# E4m.net
KiCad netlist of a schematic drawn in EAGLE
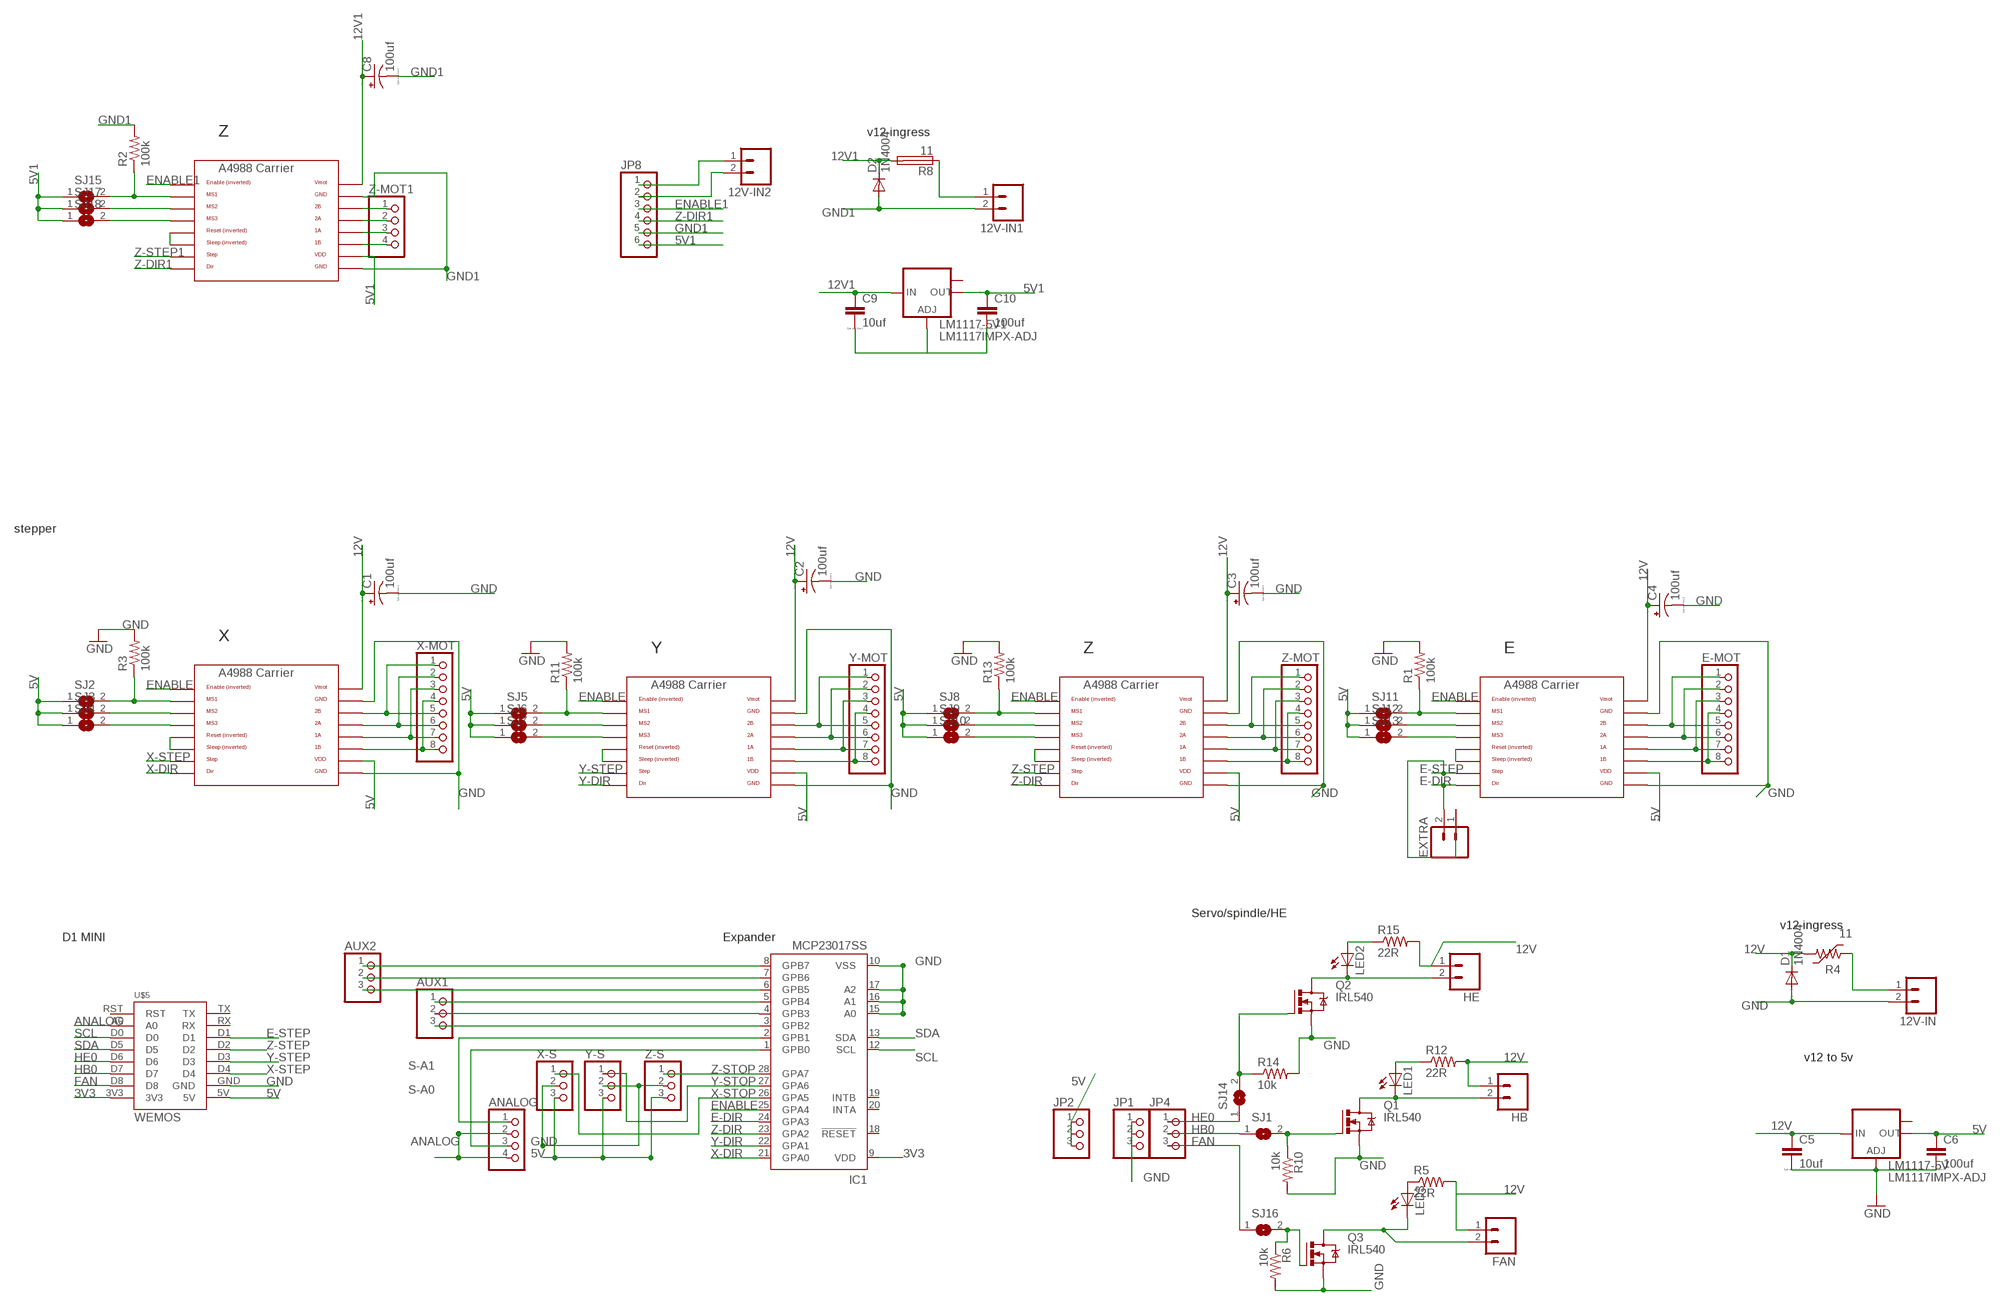
[diagram p0: schematic, sheet 1]

(export (version "E")
  (design (tool "Eeschema 10.0.6"))
  (components
    (comp (ref "12V-IN")
      (value "M02PTH")
      (footprint "eagle-import:1X02")
      (libsource (lib "eagle-import") (part "M02PTH"))
    )
    (comp (ref "12V-IN1")
      (value "M02PTH")
      (footprint "eagle-import:1X02")
      (libsource (lib "eagle-import") (part "M02PTH"))
    )
    (comp (ref "12V-IN2")
      (value "M02PTH")
      (footprint "eagle-import:1X02")
      (libsource (lib "eagle-import") (part "M02PTH"))
    )
    (comp (ref "ANALOG")
      (value "PINHD-1X4")
      (footprint "eagle-import:1X04")
      (libsource (lib "eagle-import") (part "PINHD-1X4"))
    )
    (comp (ref "AUX1")
      (value "PINHD-1X3CB")
      (footprint "eagle-import:1X03-CLEANBIG")
      (libsource (lib "eagle-import") (part "PINHD-1X3CB"))
    )
    (comp (ref "AUX2")
      (value "PINHD-1X3CB")
      (footprint "eagle-import:1X03-CLEANBIG")
      (libsource (lib "eagle-import") (part "PINHD-1X3CB"))
    )
    (comp (ref "C1")
      (value "100uf")
      (footprint "eagle-import:153CLV-0605")
      (libsource (lib "eagle-import") (part "CPOL-US153CLV-0605"))
    )
    (comp (ref "C2")
      (value "100uf")
      (footprint "eagle-import:153CLV-0605")
      (libsource (lib "eagle-import") (part "CPOL-US153CLV-0605"))
    )
    (comp (ref "C3")
      (value "100uf")
      (footprint "eagle-import:153CLV-0605")
      (libsource (lib "eagle-import") (part "CPOL-US153CLV-0605"))
    )
    (comp (ref "C4")
      (value "100uf")
      (footprint "eagle-import:153CLV-0605")
      (libsource (lib "eagle-import") (part "CPOL-US153CLV-0605"))
    )
    (comp (ref "C5")
      (value "10uf")
      (footprint "eagle-import:C0805")
      (libsource (lib "eagle-import") (part "C"))
    )
    (comp (ref "C6")
      (value "100uf")
      (footprint "eagle-import:C0805")
      (libsource (lib "eagle-import") (part "C"))
    )
    (comp (ref "C8")
      (value "100uf")
      (footprint "eagle-import:153CLV-0605")
      (libsource (lib "eagle-import") (part "CPOL-US153CLV-0605"))
    )
    (comp (ref "C9")
      (value "10uf")
      (footprint "eagle-import:C0603")
      (libsource (lib "eagle-import") (part "CC0603"))
    )
    (comp (ref "C10")
      (value "100uf")
      (footprint "eagle-import:C0603")
      (libsource (lib "eagle-import") (part "CC0603"))
    )
    (comp (ref "D1")
      (value "1N4004")
      (footprint "eagle-import:DO41-10")
      (libsource (lib "eagle-import") (part "1N4004"))
    )
    (comp (ref "D2")
      (value "1N4004")
      (footprint "eagle-import:DO41-10")
      (libsource (lib "eagle-import") (part "1N4004"))
    )
    (comp (ref "E-MOT")
      (value "PINHD-1X8CLEANBIG")
      (footprint "eagle-import:1X08-CLEANBIG")
      (libsource (lib "eagle-import") (part "PINHD-1X8CLEANBIG"))
    )
    (comp (ref "EXTRA")
      (value "M02PTH")
      (footprint "eagle-import:1X02")
      (libsource (lib "eagle-import") (part "M02PTH"))
    )
    (comp (ref "FAN")
      (value "M02PTH")
      (footprint "eagle-import:1X02")
      (libsource (lib "eagle-import") (part "M02PTH"))
    )
    (comp (ref "HB")
      (value "M02PTH")
      (footprint "eagle-import:1X02")
      (libsource (lib "eagle-import") (part "M02PTH"))
    )
    (comp (ref "HE")
      (value "M02PTH")
      (footprint "eagle-import:1X02")
      (libsource (lib "eagle-import") (part "M02PTH"))
    )
    (comp (ref "IC1")
      (value "MCP23017SS")
      (footprint "eagle-import:SSOP28")
      (libsource (lib "eagle-import") (part "MCP23017SS"))
    )
    (comp (ref "JP1")
      (value "PINHD-1X3CB")
      (footprint "eagle-import:1X03-CLEANBIG")
      (libsource (lib "eagle-import") (part "PINHD-1X3CB"))
    )
    (comp (ref "JP2")
      (value "PINHD-1X3CB")
      (footprint "eagle-import:1X03-CLEANBIG")
      (libsource (lib "eagle-import") (part "PINHD-1X3CB"))
    )
    (comp (ref "JP4")
      (value "PINHD-1X3CB")
      (footprint "eagle-import:1X03-CLEANBIG")
      (libsource (lib "eagle-import") (part "PINHD-1X3CB"))
    )
    (comp (ref "JP8")
      (value "PINHD-1X6")
      (footprint "eagle-import:1X06")
      (libsource (lib "eagle-import") (part "PINHD-1X6"))
    )
    (comp (ref "LED1")
      (value "LEDCHIP-LED0805")
      (footprint "eagle-import:CHIP-LED0805")
      (libsource (lib "eagle-import") (part "LEDCHIP-LED0805"))
    )
    (comp (ref "LED2")
      (value "LEDCHIP-LED0805")
      (footprint "eagle-import:CHIP-LED0805")
      (libsource (lib "eagle-import") (part "LEDCHIP-LED0805"))
    )
    (comp (ref "LED3")
      (value "LEDCHIP-LED0805")
      (footprint "eagle-import:CHIP-LED0805")
      (libsource (lib "eagle-import") (part "LEDCHIP-LED0805"))
    )
    (comp (ref "LM1117-5V")
      (value "LM1117IMPX-ADJ")
      (footprint "eagle-import:SOT223")
      (libsource (lib "eagle-import") (part "LM1117IMPX-ADJ"))
    )
    (comp (ref "LM1117-5V1")
      (value "LM1117IMPX-ADJ")
      (footprint "eagle-import:SOT223")
      (libsource (lib "eagle-import") (part "LM1117IMPX-ADJ"))
    )
    (comp (ref "Q1")
      (value "IRL540")
      (footprint "eagle-import:TO220BV")
      (libsource (lib "eagle-import") (part "IRF540"))
    )
    (comp (ref "Q2")
      (value "IRL540")
      (footprint "eagle-import:TO220BV")
      (libsource (lib "eagle-import") (part "IRF540"))
    )
    (comp (ref "Q3")
      (value "IRL540")
      (footprint "eagle-import:TO220BV")
      (libsource (lib "eagle-import") (part "IRF540"))
    )
    (comp (ref "R1")
      (value "100k")
      (footprint "eagle-import:R0805")
      (libsource (lib "eagle-import") (part "R-US_R0805"))
    )
    (comp (ref "R2")
      (value "100k")
      (footprint "eagle-import:R0805")
      (libsource (lib "eagle-import") (part "R-US_R0805"))
    )
    (comp (ref "R3")
      (value "100k")
      (footprint "eagle-import:R0805")
      (libsource (lib "eagle-import") (part "R-US_R0805"))
    )
    (comp (ref "R4")
      (value "11")
      (footprint "eagle-import:PF-8.0")
      (libsource (lib "eagle-import") (part "PTC-PF-8.0"))
    )
    (comp (ref "R5")
      (value "22R")
      (footprint "eagle-import:R0805")
      (libsource (lib "eagle-import") (part "R-US_R0805"))
    )
    (comp (ref "R6")
      (value "10k")
      (footprint "eagle-import:R0805")
      (libsource (lib "eagle-import") (part "R-US_R0805"))
    )
    (comp (ref "R8")
      (value "11")
      (footprint "eagle-import:LITTLEFUSE")
      (libsource (lib "eagle-import") (part "PTCFUSE"))
    )
    (comp (ref "R10")
      (value "10k")
      (footprint "eagle-import:R0805")
      (libsource (lib "eagle-import") (part "R-US_R0805"))
    )
    (comp (ref "R11")
      (value "100k")
      (footprint "eagle-import:R0805")
      (libsource (lib "eagle-import") (part "R-US_R0805"))
    )
    (comp (ref "R12")
      (value "22R")
      (footprint "eagle-import:R0805")
      (libsource (lib "eagle-import") (part "R-US_R0805"))
    )
    (comp (ref "R13")
      (value "100k")
      (footprint "eagle-import:R0805")
      (libsource (lib "eagle-import") (part "R-US_R0805"))
    )
    (comp (ref "R14")
      (value "10k")
      (footprint "eagle-import:R0805")
      (libsource (lib "eagle-import") (part "R-US_R0805"))
    )
    (comp (ref "R15")
      (value "22R")
      (footprint "eagle-import:R0805")
      (libsource (lib "eagle-import") (part "R-US_R0805"))
    )
    (comp (ref "SJ1") (value "SJ") (footprint "eagle-import:SJ") (libsource (lib "eagle-import") (part "SJ")))
    (comp (ref "SJ2") (value "SJ") (footprint "eagle-import:SJ") (libsource (lib "eagle-import") (part "SJ")))
    (comp (ref "SJ3") (value "SJ") (footprint "eagle-import:SJ") (libsource (lib "eagle-import") (part "SJ")))
    (comp (ref "SJ4") (value "SJ") (footprint "eagle-import:SJ") (libsource (lib "eagle-import") (part "SJ")))
    (comp (ref "SJ5") (value "SJ") (footprint "eagle-import:SJ") (libsource (lib "eagle-import") (part "SJ")))
    (comp (ref "SJ6") (value "SJ") (footprint "eagle-import:SJ") (libsource (lib "eagle-import") (part "SJ")))
    (comp (ref "SJ7") (value "SJ") (footprint "eagle-import:SJ") (libsource (lib "eagle-import") (part "SJ")))
    (comp (ref "SJ8") (value "SJ") (footprint "eagle-import:SJ") (libsource (lib "eagle-import") (part "SJ")))
    (comp (ref "SJ9") (value "SJ") (footprint "eagle-import:SJ") (libsource (lib "eagle-import") (part "SJ")))
    (comp (ref "SJ10")
      (value "SJ")
      (footprint "eagle-import:SJ")
      (libsource (lib "eagle-import") (part "SJ"))
    )
    (comp (ref "SJ11")
      (value "SJ")
      (footprint "eagle-import:SJ")
      (libsource (lib "eagle-import") (part "SJ"))
    )
    (comp (ref "SJ12")
      (value "SJ")
      (footprint "eagle-import:SJ")
      (libsource (lib "eagle-import") (part "SJ"))
    )
    (comp (ref "SJ13")
      (value "SJ")
      (footprint "eagle-import:SJ")
      (libsource (lib "eagle-import") (part "SJ"))
    )
    (comp (ref "SJ14")
      (value "SJ")
      (footprint "eagle-import:SJ")
      (libsource (lib "eagle-import") (part "SJ"))
    )
    (comp (ref "SJ15")
      (value "SJ")
      (footprint "eagle-import:SJ")
      (libsource (lib "eagle-import") (part "SJ"))
    )
    (comp (ref "SJ16")
      (value "SJ")
      (footprint "eagle-import:SJ")
      (libsource (lib "eagle-import") (part "SJ"))
    )
    (comp (ref "SJ17")
      (value "SJ")
      (footprint "eagle-import:SJ")
      (libsource (lib "eagle-import") (part "SJ"))
    )
    (comp (ref "SJ18")
      (value "SJ")
      (footprint "eagle-import:SJ")
      (libsource (lib "eagle-import") (part "SJ"))
    )
    (comp (ref "U$1")
      (value "A4988BREAKOUT")
      (footprint "eagle-import:A4988BREAKOUT")
      (libsource (lib "eagle-import") (part "A4988BREAKOUT"))
    )
    (comp (ref "U$2")
      (value "A4988BREAKOUT")
      (footprint "eagle-import:A4988BREAKOUT")
      (libsource (lib "eagle-import") (part "A4988BREAKOUT"))
    )
    (comp (ref "U$3")
      (value "A4988BREAKOUT")
      (footprint "eagle-import:A4988BREAKOUT")
      (libsource (lib "eagle-import") (part "A4988BREAKOUT"))
    )
    (comp (ref "U$5")
      (value "WEMOS")
      (footprint "eagle-import:WEMOS")
      (libsource (lib "eagle-import") (part "WEMOS"))
    )
    (comp (ref "U$6")
      (value "A4988BREAKOUT")
      (footprint "eagle-import:A4988BREAKOUT")
      (libsource (lib "eagle-import") (part "A4988BREAKOUT"))
    )
    (comp (ref "U$9")
      (value "A4988BREAKOUT")
      (footprint "eagle-import:A4988BREAKOUT")
      (libsource (lib "eagle-import") (part "A4988BREAKOUT"))
    )
    (comp (ref "X-MOT")
      (value "PINHD-1X8CLEANBIG")
      (footprint "eagle-import:1X08-CLEANBIG")
      (libsource (lib "eagle-import") (part "PINHD-1X8CLEANBIG"))
    )
    (comp (ref "X-S")
      (value "PINHD-1X3CB")
      (footprint "eagle-import:1X03-CLEANBIG")
      (libsource (lib "eagle-import") (part "PINHD-1X3CB"))
    )
    (comp (ref "Y-MOT")
      (value "PINHD-1X8CLEANBIG")
      (footprint "eagle-import:1X08-CLEANBIG")
      (libsource (lib "eagle-import") (part "PINHD-1X8CLEANBIG"))
    )
    (comp (ref "Y-S")
      (value "PINHD-1X3CB")
      (footprint "eagle-import:1X03-CLEANBIG")
      (libsource (lib "eagle-import") (part "PINHD-1X3CB"))
    )
    (comp (ref "Z-MOT")
      (value "PINHD-1X8CLEANBIG")
      (footprint "eagle-import:1X08-CLEANBIG")
      (libsource (lib "eagle-import") (part "PINHD-1X8CLEANBIG"))
    )
    (comp (ref "Z-MOT1")
      (value "PINHD-1X4")
      (footprint "eagle-import:1X04")
      (libsource (lib "eagle-import") (part "PINHD-1X4"))
    )
    (comp (ref "Z-S")
      (value "PINHD-1X3CB")
      (footprint "eagle-import:1X03-CLEANBIG")
      (libsource (lib "eagle-import") (part "PINHD-1X3CB"))
    )
  )
  (nets
    (net (code "1") (name "/3V3") (class "Default")
      (node (ref "IC1") (pin "9") (pinfunction "VDD_9") (pintype "power_in"))
      (node (ref "U$5") (pin "3V3") (pinfunction "3V3_3V3") (pintype "bidirectional"))
    )
    (net (code "2") (name "/5V") (class "Default")
      (node (ref "C6") (pin "1") (pinfunction "1_1") (pintype "passive"))
      (node (ref "JP2") (pin "1") (pinfunction "1_1") (pintype "passive"))
      (node (ref "JP2") (pin "2") (pinfunction "2_2") (pintype "passive"))
      (node (ref "JP2") (pin "3") (pinfunction "3_3") (pintype "passive"))
      (node (ref "LM1117-5V") (pin "2") (pinfunction "OUT_2") (pintype "passive"))
      (node (ref "SJ10") (pin "1") (pinfunction "1_1") (pintype "passive"))
      (node (ref "SJ11") (pin "1") (pinfunction "1_1") (pintype "passive"))
      (node (ref "SJ12") (pin "1") (pinfunction "1_1") (pintype "passive"))
      (node (ref "SJ13") (pin "1") (pinfunction "1_1") (pintype "passive"))
      (node (ref "SJ2") (pin "1") (pinfunction "1_1") (pintype "passive"))
      (node (ref "SJ3") (pin "1") (pinfunction "1_1") (pintype "passive"))
      (node (ref "SJ4") (pin "1") (pinfunction "1_1") (pintype "passive"))
      (node (ref "SJ5") (pin "1") (pinfunction "1_1") (pintype "passive"))
      (node (ref "SJ6") (pin "1") (pinfunction "1_1") (pintype "passive"))
      (node (ref "SJ7") (pin "1") (pinfunction "1_1") (pintype "passive"))
      (node (ref "SJ8") (pin "1") (pinfunction "1_1") (pintype "passive"))
      (node (ref "SJ9") (pin "1") (pinfunction "1_1") (pintype "passive"))
      (node (ref "U$1") (pin "VDD") (pinfunction "VDD_VDD") (pintype "power_in"))
      (node (ref "U$2") (pin "VDD") (pinfunction "VDD_VDD") (pintype "power_in"))
      (node (ref "U$3") (pin "VDD") (pinfunction "VDD_VDD") (pintype "power_in"))
      (node (ref "U$5") (pin "5V") (pinfunction "5V_5V") (pintype "bidirectional"))
      (node (ref "U$9") (pin "VDD") (pinfunction "VDD_VDD") (pintype "power_in"))
      (node (ref "X-S") (pin "3") (pinfunction "3_3") (pintype "passive"))
      (node (ref "Y-S") (pin "3") (pinfunction "3_3") (pintype "passive"))
      (node (ref "Z-S") (pin "3") (pinfunction "3_3") (pintype "passive"))
    )
    (net (code "3") (name "/5V1") (class "Default")
      (node (ref "C10") (pin "1") (pinfunction "1_1") (pintype "passive"))
      (node (ref "JP8") (pin "6") (pinfunction "6_6") (pintype "passive"))
      (node (ref "LM1117-5V1") (pin "2") (pinfunction "OUT_2") (pintype "passive"))
      (node (ref "SJ15") (pin "1") (pinfunction "1_1") (pintype "passive"))
      (node (ref "SJ17") (pin "1") (pinfunction "1_1") (pintype "passive"))
      (node (ref "SJ18") (pin "1") (pinfunction "1_1") (pintype "passive"))
      (node (ref "U$6") (pin "VDD") (pinfunction "VDD_VDD") (pintype "power_in"))
    )
    (net (code "4") (name "/12V") (class "Default")
      (node (ref "C1") (pin "+") (pinfunction "+_+") (pintype "passive"))
      (node (ref "C2") (pin "+") (pinfunction "+_+") (pintype "passive"))
      (node (ref "C3") (pin "+") (pinfunction "+_+") (pintype "passive"))
      (node (ref "C4") (pin "+") (pinfunction "+_+") (pintype "passive"))
      (node (ref "C5") (pin "1") (pinfunction "1_1") (pintype "passive"))
      (node (ref "D1") (pin "C") (pinfunction "C_C") (pintype "passive"))
      (node (ref "FAN") (pin "1") (pinfunction "1_1") (pintype "passive"))
      (node (ref "HB") (pin "1") (pinfunction "1_1") (pintype "passive"))
      (node (ref "HE") (pin "1") (pinfunction "1_1") (pintype "passive"))
      (node (ref "LM1117-5V") (pin "3") (pinfunction "IN_3") (pintype "input"))
      (node (ref "R12") (pin "2") (pinfunction "2_2") (pintype "passive"))
      (node (ref "R15") (pin "2") (pinfunction "2_2") (pintype "passive"))
      (node (ref "R4") (pin "2") (pinfunction "2_2") (pintype "passive"))
      (node (ref "R5") (pin "2") (pinfunction "2_2") (pintype "passive"))
      (node (ref "U$1") (pin "VMOT") (pinfunction "VMOT_VMOT") (pintype "power_in"))
      (node (ref "U$2") (pin "VMOT") (pinfunction "VMOT_VMOT") (pintype "power_in"))
      (node (ref "U$3") (pin "VMOT") (pinfunction "VMOT_VMOT") (pintype "power_in"))
      (node (ref "U$9") (pin "VMOT") (pinfunction "VMOT_VMOT") (pintype "power_in"))
    )
    (net (code "5") (name "/12V1") (class "Default")
      (node (ref "C8") (pin "+") (pinfunction "+_+") (pintype "passive"))
      (node (ref "C9") (pin "1") (pinfunction "1_1") (pintype "passive"))
      (node (ref "D2") (pin "C") (pinfunction "C_C") (pintype "passive"))
      (node (ref "LM1117-5V1") (pin "3") (pinfunction "IN_3") (pintype "input"))
      (node (ref "R8") (pin "2") (pinfunction "2_2") (pintype "passive"))
      (node (ref "U$6") (pin "VMOT") (pinfunction "VMOT_VMOT") (pintype "power_in"))
    )
    (net (code "6") (name "/ANALOG") (class "Default")
      (node (ref "ANALOG") (pin "2") (pinfunction "2_2") (pintype "passive"))
      (node (ref "ANALOG") (pin "4") (pinfunction "4_4") (pintype "passive"))
      (node (ref "U$5") (pin "A0") (pinfunction "A0_A0") (pintype "bidirectional"))
    )
    (net (code "7") (name "/E-DIR") (class "Default")
      (node (ref "EXTRA") (pin "2") (pinfunction "2_2") (pintype "passive"))
      (node (ref "IC1") (pin "24") (pinfunction "GPA3_24") (pintype "bidirectional"))
      (node (ref "U$2") (pin "DIR") (pinfunction "DIR_DIR") (pintype "input"))
    )
    (net (code "8") (name "/E-STEP") (class "Default")
      (node (ref "EXTRA") (pin "1") (pinfunction "1_1") (pintype "passive"))
      (node (ref "U$2") (pin "STEP") (pinfunction "STEP_STEP") (pintype "input"))
      (node (ref "U$5") (pin "D1") (pinfunction "D1_D1") (pintype "bidirectional"))
    )
    (net (code "9") (name "/ENABLE") (class "Default")
      (node (ref "IC1") (pin "25") (pinfunction "GPA4_25") (pintype "bidirectional"))
      (node (ref "U$1") (pin "EN") (pinfunction "EN_EN") (pintype "input"))
      (node (ref "U$2") (pin "EN") (pinfunction "EN_EN") (pintype "input"))
      (node (ref "U$3") (pin "EN") (pinfunction "EN_EN") (pintype "input"))
      (node (ref "U$9") (pin "EN") (pinfunction "EN_EN") (pintype "input"))
    )
    (net (code "10") (name "/ENABLE1") (class "Default")
      (node (ref "JP8") (pin "3") (pinfunction "3_3") (pintype "passive"))
      (node (ref "U$6") (pin "EN") (pinfunction "EN_EN") (pintype "input"))
    )
    (net (code "11") (name "/FAN") (class "Default")
      (node (ref "JP4") (pin "3") (pinfunction "3_3") (pintype "passive"))
      (node (ref "SJ16") (pin "1") (pinfunction "1_1") (pintype "passive"))
      (node (ref "U$5") (pin "D8") (pinfunction "D8_D8") (pintype "bidirectional"))
    )
    (net (code "12") (name "/GND1") (class "Default")
      (node (ref "12V-IN1") (pin "2") (pinfunction "2_2") (pintype "passive"))
      (node (ref "C8") (pin "-") (pinfunction "-_-") (pintype "passive"))
      (node (ref "D2") (pin "A") (pinfunction "A_A") (pintype "passive"))
      (node (ref "JP8") (pin "5") (pinfunction "5_5") (pintype "passive"))
      (node (ref "R2") (pin "2") (pinfunction "2_2") (pintype "passive"))
      (node (ref "U$6") (pin "GND") (pinfunction "GND_GND") (pintype "power_in"))
      (node (ref "U$6") (pin "GND@0") (pinfunction "GND_GND@0") (pintype "power_in"))
    )
    (net (code "13") (name "/HB0") (class "Default")
      (node (ref "JP4") (pin "2") (pinfunction "2_2") (pintype "passive"))
      (node (ref "SJ1") (pin "1") (pinfunction "1_1") (pintype "passive"))
      (node (ref "U$5") (pin "D7") (pinfunction "D7_D7") (pintype "bidirectional"))
    )
    (net (code "14") (name "/HE0") (class "Default")
      (node (ref "JP4") (pin "1") (pinfunction "1_1") (pintype "passive"))
      (node (ref "SJ14") (pin "1") (pinfunction "1_1") (pintype "passive"))
      (node (ref "U$5") (pin "D6") (pinfunction "D6_D6") (pintype "bidirectional"))
    )
    (net (code "15") (name "/S-A0") (class "Default")
      (node (ref "ANALOG") (pin "3") (pinfunction "3_3") (pintype "passive"))
      (node (ref "IC1") (pin "1") (pinfunction "GPB0_1") (pintype "bidirectional"))
    )
    (net (code "16") (name "/S-A1") (class "Default")
      (node (ref "ANALOG") (pin "1") (pinfunction "1_1") (pintype "passive"))
      (node (ref "IC1") (pin "2") (pinfunction "GPB1_2") (pintype "bidirectional"))
    )
    (net (code "17") (name "/SCL") (class "Default")
      (node (ref "IC1") (pin "12") (pinfunction "SCL_12") (pintype "input"))
      (node (ref "U$5") (pin "D0") (pinfunction "D0_D0") (pintype "bidirectional"))
    )
    (net (code "18") (name "/SDA") (class "Default")
      (node (ref "IC1") (pin "13") (pinfunction "SDA_13") (pintype "bidirectional"))
      (node (ref "U$5") (pin "D5") (pinfunction "D5_D5") (pintype "bidirectional"))
    )
    (net (code "19") (name "/X-DIR") (class "Default")
      (node (ref "IC1") (pin "21") (pinfunction "GPA0_21") (pintype "bidirectional"))
      (node (ref "U$1") (pin "DIR") (pinfunction "DIR_DIR") (pintype "input"))
    )
    (net (code "20") (name "/X-STEP") (class "Default")
      (node (ref "U$1") (pin "STEP") (pinfunction "STEP_STEP") (pintype "input"))
      (node (ref "U$5") (pin "D4") (pinfunction "D4_D4") (pintype "bidirectional"))
    )
    (net (code "21") (name "/X-STOP") (class "Default")
      (node (ref "IC1") (pin "26") (pinfunction "GPA5_26") (pintype "bidirectional"))
      (node (ref "X-S") (pin "1") (pinfunction "1_1") (pintype "passive"))
    )
    (net (code "22") (name "/Y-DIR") (class "Default")
      (node (ref "IC1") (pin "22") (pinfunction "GPA1_22") (pintype "bidirectional"))
      (node (ref "U$3") (pin "DIR") (pinfunction "DIR_DIR") (pintype "input"))
    )
    (net (code "23") (name "/Y-STEP") (class "Default")
      (node (ref "U$3") (pin "STEP") (pinfunction "STEP_STEP") (pintype "input"))
      (node (ref "U$5") (pin "D3") (pinfunction "D3_D3") (pintype "bidirectional"))
    )
    (net (code "24") (name "/Y-STOP") (class "Default")
      (node (ref "IC1") (pin "27") (pinfunction "GPA6_27") (pintype "bidirectional"))
      (node (ref "Y-S") (pin "1") (pinfunction "1_1") (pintype "passive"))
    )
    (net (code "25") (name "/Z-DIR") (class "Default")
      (node (ref "IC1") (pin "23") (pinfunction "GPA2_23") (pintype "bidirectional"))
      (node (ref "U$9") (pin "DIR") (pinfunction "DIR_DIR") (pintype "input"))
    )
    (net (code "26") (name "/Z-DIR1") (class "Default")
      (node (ref "JP8") (pin "4") (pinfunction "4_4") (pintype "passive"))
      (node (ref "U$6") (pin "DIR") (pinfunction "DIR_DIR") (pintype "input"))
    )
    (net (code "27") (name "/Z-STEP") (class "Default")
      (node (ref "U$5") (pin "D2") (pinfunction "D2_D2") (pintype "bidirectional"))
      (node (ref "U$9") (pin "STEP") (pinfunction "STEP_STEP") (pintype "input"))
    )
    (net (code "28") (name "/Z-STEP1") (class "Default")
      (node (ref "U$6") (pin "STEP") (pinfunction "STEP_STEP") (pintype "input"))
    )
    (net (code "29") (name "/Z-STOP") (class "Default")
      (node (ref "IC1") (pin "28") (pinfunction "GPA7_28") (pintype "bidirectional"))
      (node (ref "Z-S") (pin "1") (pinfunction "1_1") (pintype "passive"))
    )
    (net (code "30") (name "GND") (class "Default")
      (node (ref "12V-IN") (pin "2") (pinfunction "2_2") (pintype "passive"))
      (node (ref "C1") (pin "-") (pinfunction "-_-") (pintype "passive"))
      (node (ref "C2") (pin "-") (pinfunction "-_-") (pintype "passive"))
      (node (ref "C3") (pin "-") (pinfunction "-_-") (pintype "passive"))
      (node (ref "C4") (pin "-") (pinfunction "-_-") (pintype "passive"))
      (node (ref "C5") (pin "2") (pinfunction "2_2") (pintype "passive"))
      (node (ref "C6") (pin "2") (pinfunction "2_2") (pintype "passive"))
      (node (ref "D1") (pin "A") (pinfunction "A_A") (pintype "passive"))
      (node (ref "IC1") (pin "10") (pinfunction "VSS_10") (pintype "power_in"))
      (node (ref "IC1") (pin "15") (pinfunction "A0_15") (pintype "input"))
      (node (ref "IC1") (pin "16") (pinfunction "A1_16") (pintype "input"))
      (node (ref "IC1") (pin "17") (pinfunction "A2_17") (pintype "input"))
      (node (ref "JP1") (pin "1") (pinfunction "1_1") (pintype "passive"))
      (node (ref "JP1") (pin "2") (pinfunction "2_2") (pintype "passive"))
      (node (ref "JP1") (pin "3") (pinfunction "3_3") (pintype "passive"))
      (node (ref "LM1117-5V") (pin "1") (pinfunction "ADJ_1") (pintype "input"))
      (node (ref "Q1") (pin "S") (pinfunction "S_S") (pintype "passive"))
      (node (ref "Q2") (pin "S") (pinfunction "S_S") (pintype "passive"))
      (node (ref "Q3") (pin "S") (pinfunction "S_S") (pintype "passive"))
      (node (ref "R1") (pin "2") (pinfunction "2_2") (pintype "passive"))
      (node (ref "R10") (pin "2") (pinfunction "2_2") (pintype "passive"))
      (node (ref "R11") (pin "2") (pinfunction "2_2") (pintype "passive"))
      (node (ref "R13") (pin "2") (pinfunction "2_2") (pintype "passive"))
      (node (ref "R14") (pin "2") (pinfunction "2_2") (pintype "passive"))
      (node (ref "R3") (pin "2") (pinfunction "2_2") (pintype "passive"))
      (node (ref "R6") (pin "2") (pinfunction "2_2") (pintype "passive"))
      (node (ref "U$1") (pin "GND") (pinfunction "GND_GND") (pintype "power_in"))
      (node (ref "U$1") (pin "GND@0") (pinfunction "GND_GND@0") (pintype "power_in"))
      (node (ref "U$2") (pin "GND") (pinfunction "GND_GND") (pintype "power_in"))
      (node (ref "U$2") (pin "GND@0") (pinfunction "GND_GND@0") (pintype "power_in"))
      (node (ref "U$3") (pin "GND") (pinfunction "GND_GND") (pintype "power_in"))
      (node (ref "U$3") (pin "GND@0") (pinfunction "GND_GND@0") (pintype "power_in"))
      (node (ref "U$5") (pin "GND") (pinfunction "GND_GND") (pintype "bidirectional"))
      (node (ref "U$9") (pin "GND") (pinfunction "GND_GND") (pintype "power_in"))
      (node (ref "U$9") (pin "GND@0") (pinfunction "GND_GND@0") (pintype "power_in"))
      (node (ref "X-S") (pin "2") (pinfunction "2_2") (pintype "passive"))
      (node (ref "Y-S") (pin "2") (pinfunction "2_2") (pintype "passive"))
      (node (ref "Z-S") (pin "2") (pinfunction "2_2") (pintype "passive"))
    )
    (net (code "31") (name "Net-(12V-IN-Pad1)") (class "Default")
      (node (ref "12V-IN") (pin "1") (pinfunction "1_1") (pintype "passive"))
      (node (ref "R4") (pin "1") (pinfunction "1_1") (pintype "passive"))
    )
    (net (code "32") (name "Net-(12V-IN1-Pad1)") (class "Default")
      (node (ref "12V-IN1") (pin "1") (pinfunction "1_1") (pintype "passive"))
      (node (ref "R8") (pin "1") (pinfunction "1_1") (pintype "passive"))
    )
    (net (code "33") (name "Net-(12V-IN2-Pad1)") (class "Default")
      (node (ref "12V-IN2") (pin "1") (pinfunction "1_1") (pintype "passive"))
      (node (ref "JP8") (pin "1") (pinfunction "1_1") (pintype "passive"))
    )
    (net (code "34") (name "Net-(12V-IN2-Pad2)") (class "Default")
      (node (ref "12V-IN2") (pin "2") (pinfunction "2_2") (pintype "passive"))
      (node (ref "JP8") (pin "2") (pinfunction "2_2") (pintype "passive"))
    )
    (net (code "35") (name "Net-(E-MOT-Pad1)") (class "Default")
      (node (ref "E-MOT") (pin "1") (pinfunction "1_1") (pintype "passive"))
      (node (ref "E-MOT") (pin "5") (pinfunction "5_5") (pintype "passive"))
      (node (ref "U$2") (pin "2B") (pinfunction "2B_2B") (pintype "output"))
    )
    (net (code "36") (name "Net-(E-MOT-Pad2)") (class "Default")
      (node (ref "E-MOT") (pin "2") (pinfunction "2_2") (pintype "passive"))
      (node (ref "E-MOT") (pin "6") (pinfunction "6_6") (pintype "passive"))
      (node (ref "U$2") (pin "2A") (pinfunction "2A_2A") (pintype "output"))
    )
    (net (code "37") (name "Net-(E-MOT-Pad3)") (class "Default")
      (node (ref "E-MOT") (pin "3") (pinfunction "3_3") (pintype "passive"))
      (node (ref "E-MOT") (pin "7") (pinfunction "7_7") (pintype "passive"))
      (node (ref "U$2") (pin "1A") (pinfunction "1A_1A") (pintype "output"))
    )
    (net (code "38") (name "Net-(E-MOT-Pad4)") (class "Default")
      (node (ref "E-MOT") (pin "4") (pinfunction "4_4") (pintype "passive"))
      (node (ref "E-MOT") (pin "8") (pinfunction "8_8") (pintype "passive"))
      (node (ref "U$2") (pin "1B") (pinfunction "1B_1B") (pintype "output"))
    )
    (net (code "39") (name "Net-(FAN-Pad2)") (class "Default")
      (node (ref "FAN") (pin "2") (pinfunction "2_2") (pintype "passive"))
      (node (ref "LED3") (pin "C") (pinfunction "C_C") (pintype "passive"))
      (node (ref "Q3") (pin "D") (pinfunction "D_D") (pintype "passive"))
    )
    (net (code "40") (name "Net-(HB-Pad2)") (class "Default")
      (node (ref "HB") (pin "2") (pinfunction "2_2") (pintype "passive"))
      (node (ref "LED1") (pin "C") (pinfunction "C_C") (pintype "passive"))
      (node (ref "Q1") (pin "D") (pinfunction "D_D") (pintype "passive"))
    )
    (net (code "41") (name "Net-(HE-Pad2)") (class "Default")
      (node (ref "HE") (pin "2") (pinfunction "2_2") (pintype "passive"))
      (node (ref "LED2") (pin "C") (pinfunction "C_C") (pintype "passive"))
      (node (ref "Q2") (pin "D") (pinfunction "D_D") (pintype "passive"))
    )
    (net (code "42") (name "Net-(IC1-GPB2)") (class "Default")
      (node (ref "AUX1") (pin "3") (pinfunction "3_3") (pintype "passive"))
      (node (ref "IC1") (pin "3") (pinfunction "GPB2_3") (pintype "bidirectional"))
    )
    (net (code "43") (name "Net-(IC1-GPB3)") (class "Default")
      (node (ref "AUX1") (pin "2") (pinfunction "2_2") (pintype "passive"))
      (node (ref "IC1") (pin "4") (pinfunction "GPB3_4") (pintype "bidirectional"))
    )
    (net (code "44") (name "Net-(IC1-GPB4)") (class "Default")
      (node (ref "AUX1") (pin "1") (pinfunction "1_1") (pintype "passive"))
      (node (ref "IC1") (pin "5") (pinfunction "GPB4_5") (pintype "bidirectional"))
    )
    (net (code "45") (name "Net-(IC1-GPB5)") (class "Default")
      (node (ref "AUX2") (pin "3") (pinfunction "3_3") (pintype "passive"))
      (node (ref "IC1") (pin "6") (pinfunction "GPB5_6") (pintype "bidirectional"))
    )
    (net (code "46") (name "Net-(IC1-GPB6)") (class "Default")
      (node (ref "AUX2") (pin "2") (pinfunction "2_2") (pintype "passive"))
      (node (ref "IC1") (pin "7") (pinfunction "GPB6_7") (pintype "bidirectional"))
    )
    (net (code "47") (name "Net-(IC1-GPB7)") (class "Default")
      (node (ref "AUX2") (pin "1") (pinfunction "1_1") (pintype "passive"))
      (node (ref "IC1") (pin "8") (pinfunction "GPB7_8") (pintype "bidirectional"))
    )
    (net (code "48") (name "Net-(LED1-PadA)") (class "Default")
      (node (ref "LED1") (pin "A") (pinfunction "A_A") (pintype "passive"))
      (node (ref "R12") (pin "1") (pinfunction "1_1") (pintype "passive"))
    )
    (net (code "49") (name "Net-(LED2-PadA)") (class "Default")
      (node (ref "LED2") (pin "A") (pinfunction "A_A") (pintype "passive"))
      (node (ref "R15") (pin "1") (pinfunction "1_1") (pintype "passive"))
    )
    (net (code "50") (name "Net-(LED3-PadA)") (class "Default")
      (node (ref "LED3") (pin "A") (pinfunction "A_A") (pintype "passive"))
      (node (ref "R5") (pin "1") (pinfunction "1_1") (pintype "passive"))
    )
    (net (code "51") (name "Net-(LM1117-5V1-ADJ)") (class "Default")
      (node (ref "C10") (pin "2") (pinfunction "2_2") (pintype "passive"))
      (node (ref "C9") (pin "2") (pinfunction "2_2") (pintype "passive"))
      (node (ref "LM1117-5V1") (pin "1") (pinfunction "ADJ_1") (pintype "input"))
    )
    (net (code "52") (name "Net-(Q1-PadG)") (class "Default")
      (node (ref "Q1") (pin "G") (pinfunction "G_G") (pintype "passive"))
      (node (ref "R10") (pin "1") (pinfunction "1_1") (pintype "passive"))
      (node (ref "SJ1") (pin "2") (pinfunction "2_2") (pintype "passive"))
    )
    (net (code "53") (name "Net-(Q2-PadG)") (class "Default")
      (node (ref "Q2") (pin "G") (pinfunction "G_G") (pintype "passive"))
      (node (ref "R14") (pin "1") (pinfunction "1_1") (pintype "passive"))
      (node (ref "SJ14") (pin "2") (pinfunction "2_2") (pintype "passive"))
    )
    (net (code "54") (name "Net-(Q3-PadG)") (class "Default")
      (node (ref "Q3") (pin "G") (pinfunction "G_G") (pintype "passive"))
      (node (ref "R6") (pin "1") (pinfunction "1_1") (pintype "passive"))
      (node (ref "SJ16") (pin "2") (pinfunction "2_2") (pintype "passive"))
    )
    (net (code "55") (name "Net-(R1-Pad1)") (class "Default")
      (node (ref "R1") (pin "1") (pinfunction "1_1") (pintype "passive"))
      (node (ref "SJ11") (pin "2") (pinfunction "2_2") (pintype "passive"))
      (node (ref "U$2") (pin "MS1") (pinfunction "MS1_MS1") (pintype "input"))
    )
    (net (code "56") (name "Net-(R2-Pad1)") (class "Default")
      (node (ref "R2") (pin "1") (pinfunction "1_1") (pintype "passive"))
      (node (ref "SJ15") (pin "2") (pinfunction "2_2") (pintype "passive"))
      (node (ref "U$6") (pin "MS1") (pinfunction "MS1_MS1") (pintype "input"))
    )
    (net (code "57") (name "Net-(R3-Pad1)") (class "Default")
      (node (ref "R3") (pin "1") (pinfunction "1_1") (pintype "passive"))
      (node (ref "SJ2") (pin "2") (pinfunction "2_2") (pintype "passive"))
      (node (ref "U$1") (pin "MS1") (pinfunction "MS1_MS1") (pintype "input"))
    )
    (net (code "58") (name "Net-(R11-Pad1)") (class "Default")
      (node (ref "R11") (pin "1") (pinfunction "1_1") (pintype "passive"))
      (node (ref "SJ5") (pin "2") (pinfunction "2_2") (pintype "passive"))
      (node (ref "U$3") (pin "MS1") (pinfunction "MS1_MS1") (pintype "input"))
    )
    (net (code "59") (name "Net-(R13-Pad1)") (class "Default")
      (node (ref "R13") (pin "1") (pinfunction "1_1") (pintype "passive"))
      (node (ref "SJ8") (pin "2") (pinfunction "2_2") (pintype "passive"))
      (node (ref "U$9") (pin "MS1") (pinfunction "MS1_MS1") (pintype "input"))
    )
    (net (code "60") (name "Net-(SJ3-Pad2)") (class "Default")
      (node (ref "SJ3") (pin "2") (pinfunction "2_2") (pintype "passive"))
      (node (ref "U$1") (pin "MS2") (pinfunction "MS2_MS2") (pintype "input"))
    )
    (net (code "61") (name "Net-(SJ4-Pad2)") (class "Default")
      (node (ref "SJ4") (pin "2") (pinfunction "2_2") (pintype "passive"))
      (node (ref "U$1") (pin "MS3") (pinfunction "MS3_MS3") (pintype "input"))
    )
    (net (code "62") (name "Net-(SJ6-Pad2)") (class "Default")
      (node (ref "SJ6") (pin "2") (pinfunction "2_2") (pintype "passive"))
      (node (ref "U$3") (pin "MS2") (pinfunction "MS2_MS2") (pintype "input"))
    )
    (net (code "63") (name "Net-(SJ7-Pad2)") (class "Default")
      (node (ref "SJ7") (pin "2") (pinfunction "2_2") (pintype "passive"))
      (node (ref "U$3") (pin "MS3") (pinfunction "MS3_MS3") (pintype "input"))
    )
    (net (code "64") (name "Net-(SJ9-Pad2)") (class "Default")
      (node (ref "SJ9") (pin "2") (pinfunction "2_2") (pintype "passive"))
      (node (ref "U$9") (pin "MS2") (pinfunction "MS2_MS2") (pintype "input"))
    )
    (net (code "65") (name "Net-(SJ10-Pad2)") (class "Default")
      (node (ref "SJ10") (pin "2") (pinfunction "2_2") (pintype "passive"))
      (node (ref "U$9") (pin "MS3") (pinfunction "MS3_MS3") (pintype "input"))
    )
    (net (code "66") (name "Net-(SJ12-Pad2)") (class "Default")
      (node (ref "SJ12") (pin "2") (pinfunction "2_2") (pintype "passive"))
      (node (ref "U$2") (pin "MS2") (pinfunction "MS2_MS2") (pintype "input"))
    )
    (net (code "67") (name "Net-(SJ13-Pad2)") (class "Default")
      (node (ref "SJ13") (pin "2") (pinfunction "2_2") (pintype "passive"))
      (node (ref "U$2") (pin "MS3") (pinfunction "MS3_MS3") (pintype "input"))
    )
    (net (code "68") (name "Net-(SJ17-Pad2)") (class "Default")
      (node (ref "SJ17") (pin "2") (pinfunction "2_2") (pintype "passive"))
      (node (ref "U$6") (pin "MS2") (pinfunction "MS2_MS2") (pintype "input"))
    )
    (net (code "69") (name "Net-(SJ18-Pad2)") (class "Default")
      (node (ref "SJ18") (pin "2") (pinfunction "2_2") (pintype "passive"))
      (node (ref "U$6") (pin "MS3") (pinfunction "MS3_MS3") (pintype "input"))
    )
    (net (code "70") (name "Net-(U$1-Pad1A)") (class "Default")
      (node (ref "U$1") (pin "1A") (pinfunction "1A_1A") (pintype "output"))
      (node (ref "X-MOT") (pin "3") (pinfunction "3_3") (pintype "passive"))
      (node (ref "X-MOT") (pin "7") (pinfunction "7_7") (pintype "passive"))
    )
    (net (code "71") (name "Net-(U$1-Pad1B)") (class "Default")
      (node (ref "U$1") (pin "1B") (pinfunction "1B_1B") (pintype "output"))
      (node (ref "X-MOT") (pin "4") (pinfunction "4_4") (pintype "passive"))
      (node (ref "X-MOT") (pin "8") (pinfunction "8_8") (pintype "passive"))
    )
    (net (code "72") (name "Net-(U$1-Pad2A)") (class "Default")
      (node (ref "U$1") (pin "2A") (pinfunction "2A_2A") (pintype "output"))
      (node (ref "X-MOT") (pin "2") (pinfunction "2_2") (pintype "passive"))
      (node (ref "X-MOT") (pin "6") (pinfunction "6_6") (pintype "passive"))
    )
    (net (code "73") (name "Net-(U$1-Pad2B)") (class "Default")
      (node (ref "U$1") (pin "2B") (pinfunction "2B_2B") (pintype "output"))
      (node (ref "X-MOT") (pin "1") (pinfunction "1_1") (pintype "passive"))
      (node (ref "X-MOT") (pin "5") (pinfunction "5_5") (pintype "passive"))
    )
    (net (code "74") (name "Net-(U$1-SLEEP)") (class "Default")
      (node (ref "U$1") (pin "RST") (pinfunction "RST_RST") (pintype "input"))
      (node (ref "U$1") (pin "SLP") (pinfunction "SLEEP_SLP") (pintype "input"))
    )
    (net (code "75") (name "Net-(U$2-SLEEP)") (class "Default")
      (node (ref "U$2") (pin "RST") (pinfunction "RST_RST") (pintype "input"))
      (node (ref "U$2") (pin "SLP") (pinfunction "SLEEP_SLP") (pintype "input"))
    )
    (net (code "76") (name "Net-(U$3-Pad1A)") (class "Default")
      (node (ref "U$3") (pin "1A") (pinfunction "1A_1A") (pintype "output"))
      (node (ref "Y-MOT") (pin "3") (pinfunction "3_3") (pintype "passive"))
      (node (ref "Y-MOT") (pin "7") (pinfunction "7_7") (pintype "passive"))
    )
    (net (code "77") (name "Net-(U$3-Pad1B)") (class "Default")
      (node (ref "U$3") (pin "1B") (pinfunction "1B_1B") (pintype "output"))
      (node (ref "Y-MOT") (pin "4") (pinfunction "4_4") (pintype "passive"))
      (node (ref "Y-MOT") (pin "8") (pinfunction "8_8") (pintype "passive"))
    )
    (net (code "78") (name "Net-(U$3-Pad2A)") (class "Default")
      (node (ref "U$3") (pin "2A") (pinfunction "2A_2A") (pintype "output"))
      (node (ref "Y-MOT") (pin "2") (pinfunction "2_2") (pintype "passive"))
      (node (ref "Y-MOT") (pin "6") (pinfunction "6_6") (pintype "passive"))
    )
    (net (code "79") (name "Net-(U$3-Pad2B)") (class "Default")
      (node (ref "U$3") (pin "2B") (pinfunction "2B_2B") (pintype "output"))
      (node (ref "Y-MOT") (pin "1") (pinfunction "1_1") (pintype "passive"))
      (node (ref "Y-MOT") (pin "5") (pinfunction "5_5") (pintype "passive"))
    )
    (net (code "80") (name "Net-(U$3-SLEEP)") (class "Default")
      (node (ref "U$3") (pin "RST") (pinfunction "RST_RST") (pintype "input"))
      (node (ref "U$3") (pin "SLP") (pinfunction "SLEEP_SLP") (pintype "input"))
    )
    (net (code "81") (name "Net-(U$6-Pad1A)") (class "Default")
      (node (ref "U$6") (pin "1A") (pinfunction "1A_1A") (pintype "output"))
      (node (ref "Z-MOT1") (pin "3") (pinfunction "3_3") (pintype "passive"))
    )
    (net (code "82") (name "Net-(U$6-Pad1B)") (class "Default")
      (node (ref "U$6") (pin "1B") (pinfunction "1B_1B") (pintype "output"))
      (node (ref "Z-MOT1") (pin "4") (pinfunction "4_4") (pintype "passive"))
    )
    (net (code "83") (name "Net-(U$6-Pad2A)") (class "Default")
      (node (ref "U$6") (pin "2A") (pinfunction "2A_2A") (pintype "output"))
      (node (ref "Z-MOT1") (pin "2") (pinfunction "2_2") (pintype "passive"))
    )
    (net (code "84") (name "Net-(U$6-Pad2B)") (class "Default")
      (node (ref "U$6") (pin "2B") (pinfunction "2B_2B") (pintype "output"))
      (node (ref "Z-MOT1") (pin "1") (pinfunction "1_1") (pintype "passive"))
    )
    (net (code "85") (name "Net-(U$6-SLEEP)") (class "Default")
      (node (ref "U$6") (pin "RST") (pinfunction "RST_RST") (pintype "input"))
      (node (ref "U$6") (pin "SLP") (pinfunction "SLEEP_SLP") (pintype "input"))
    )
    (net (code "86") (name "Net-(U$9-Pad1A)") (class "Default")
      (node (ref "U$9") (pin "1A") (pinfunction "1A_1A") (pintype "output"))
      (node (ref "Z-MOT") (pin "3") (pinfunction "3_3") (pintype "passive"))
      (node (ref "Z-MOT") (pin "7") (pinfunction "7_7") (pintype "passive"))
    )
    (net (code "87") (name "Net-(U$9-Pad1B)") (class "Default")
      (node (ref "U$9") (pin "1B") (pinfunction "1B_1B") (pintype "output"))
      (node (ref "Z-MOT") (pin "4") (pinfunction "4_4") (pintype "passive"))
      (node (ref "Z-MOT") (pin "8") (pinfunction "8_8") (pintype "passive"))
    )
    (net (code "88") (name "Net-(U$9-Pad2A)") (class "Default")
      (node (ref "U$9") (pin "2A") (pinfunction "2A_2A") (pintype "output"))
      (node (ref "Z-MOT") (pin "2") (pinfunction "2_2") (pintype "passive"))
      (node (ref "Z-MOT") (pin "6") (pinfunction "6_6") (pintype "passive"))
    )
    (net (code "89") (name "Net-(U$9-Pad2B)") (class "Default")
      (node (ref "U$9") (pin "2B") (pinfunction "2B_2B") (pintype "output"))
      (node (ref "Z-MOT") (pin "1") (pinfunction "1_1") (pintype "passive"))
      (node (ref "Z-MOT") (pin "5") (pinfunction "5_5") (pintype "passive"))
    )
    (net (code "90") (name "Net-(U$9-SLEEP)") (class "Default")
      (node (ref "U$9") (pin "RST") (pinfunction "RST_RST") (pintype "input"))
      (node (ref "U$9") (pin "SLP") (pinfunction "SLEEP_SLP") (pintype "input"))
    )
    (net (code "91") (name "unconnected-(IC1-INTA-Pad20)") (class "Default")
      (node (ref "IC1") (pin "20") (pinfunction "INTA_20") (pintype "output"))
    )
    (net (code "92") (name "unconnected-(IC1-INTB-Pad19)") (class "Default")
      (node (ref "IC1") (pin "19") (pinfunction "INTB_19") (pintype "output"))
    )
    (net (code "93") (name "unconnected-(IC1-~{RESET}-Pad18)") (class "Default")
      (node (ref "IC1") (pin "18") (pinfunction "~{RESET}_18") (pintype "input"))
    )
    (net (code "94") (name "unconnected-(LM1117-5V-OUT1-PadTAB)") (class "Default")
      (node (ref "LM1117-5V") (pin "TAB") (pinfunction "OUT1_TAB") (pintype "passive"))
    )
    (net (code "95") (name "unconnected-(LM1117-5V1-OUT1-PadTAB)") (class "Default")
      (node (ref "LM1117-5V1") (pin "TAB") (pinfunction "OUT1_TAB") (pintype "passive"))
    )
    (net (code "96") (name "unconnected-(U$5-PadRST)") (class "Default")
      (node (ref "U$5") (pin "RST") (pinfunction "RST_RST") (pintype "bidirectional"))
    )
    (net (code "97") (name "unconnected-(U$5-PadRX)") (class "Default")
      (node (ref "U$5") (pin "RX") (pinfunction "RX_RX") (pintype "bidirectional"))
    )
    (net (code "98") (name "unconnected-(U$5-PadTX)") (class "Default")
      (node (ref "U$5") (pin "TX") (pinfunction "TX_TX") (pintype "bidirectional"))
    )
  )
)
